# sap_flux-v21.net
KiCad netlist of a schematic drawn in EAGLE
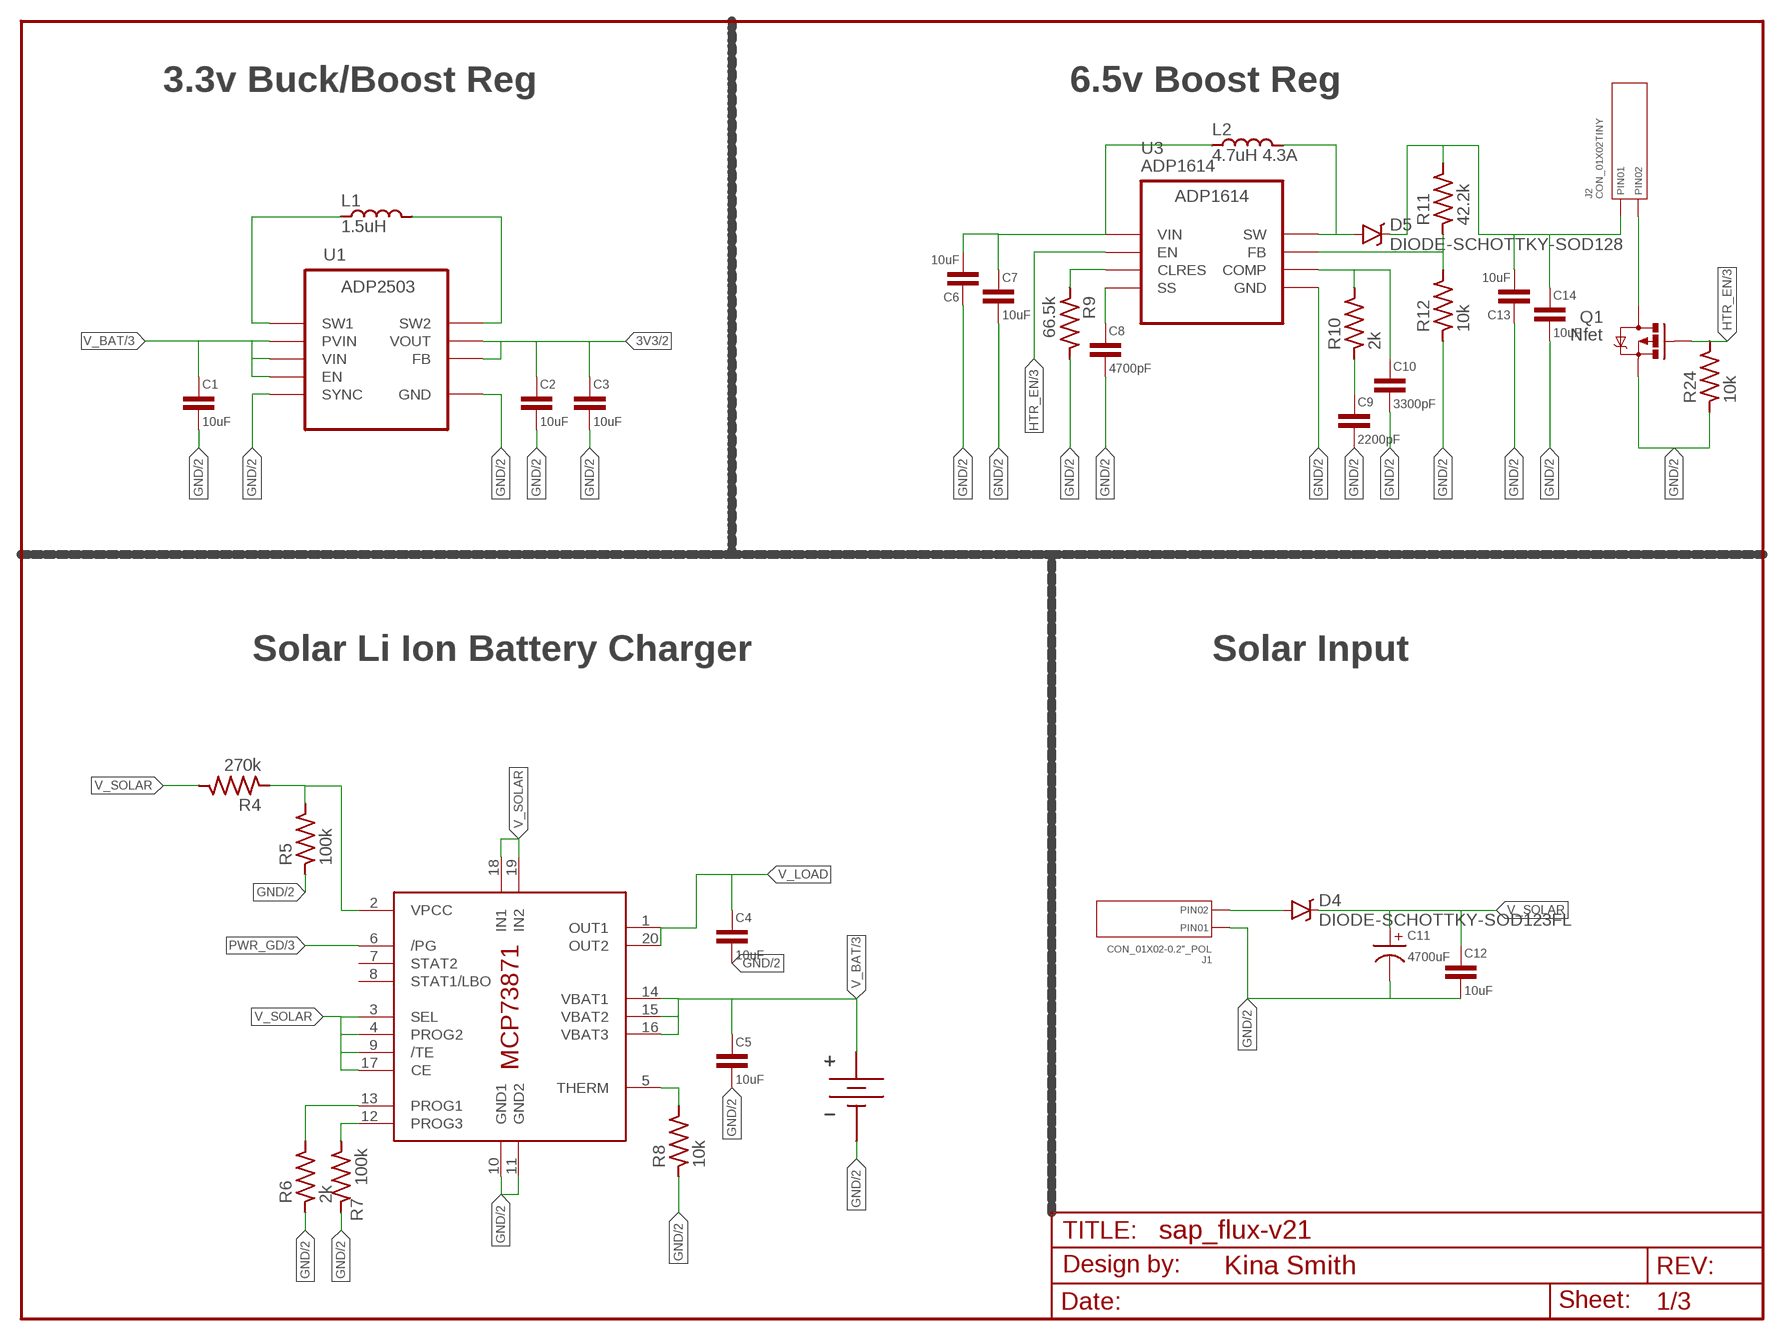
[diagram p0: schematic, sheet 1]
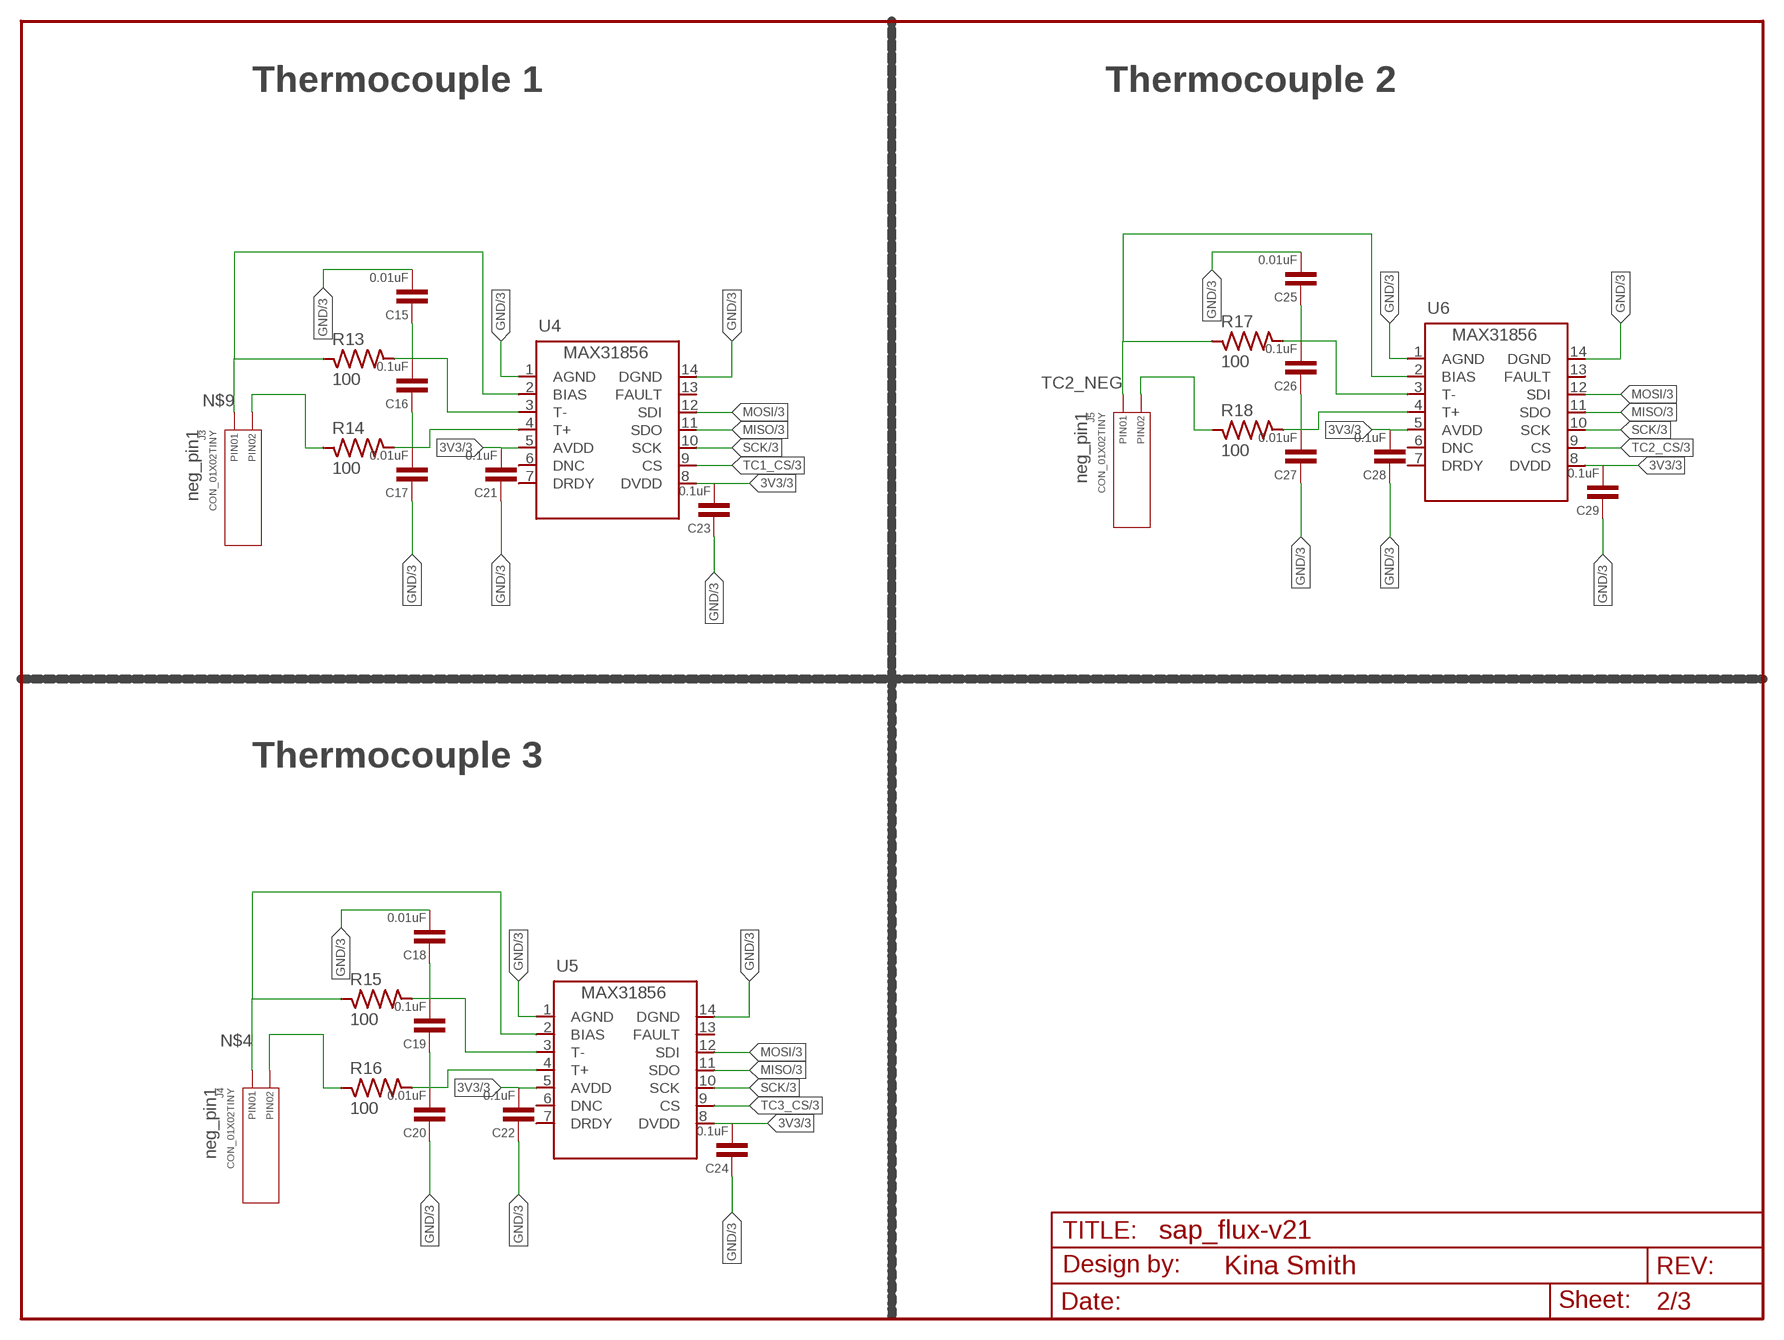
[diagram p1: schematic, sheet 2]
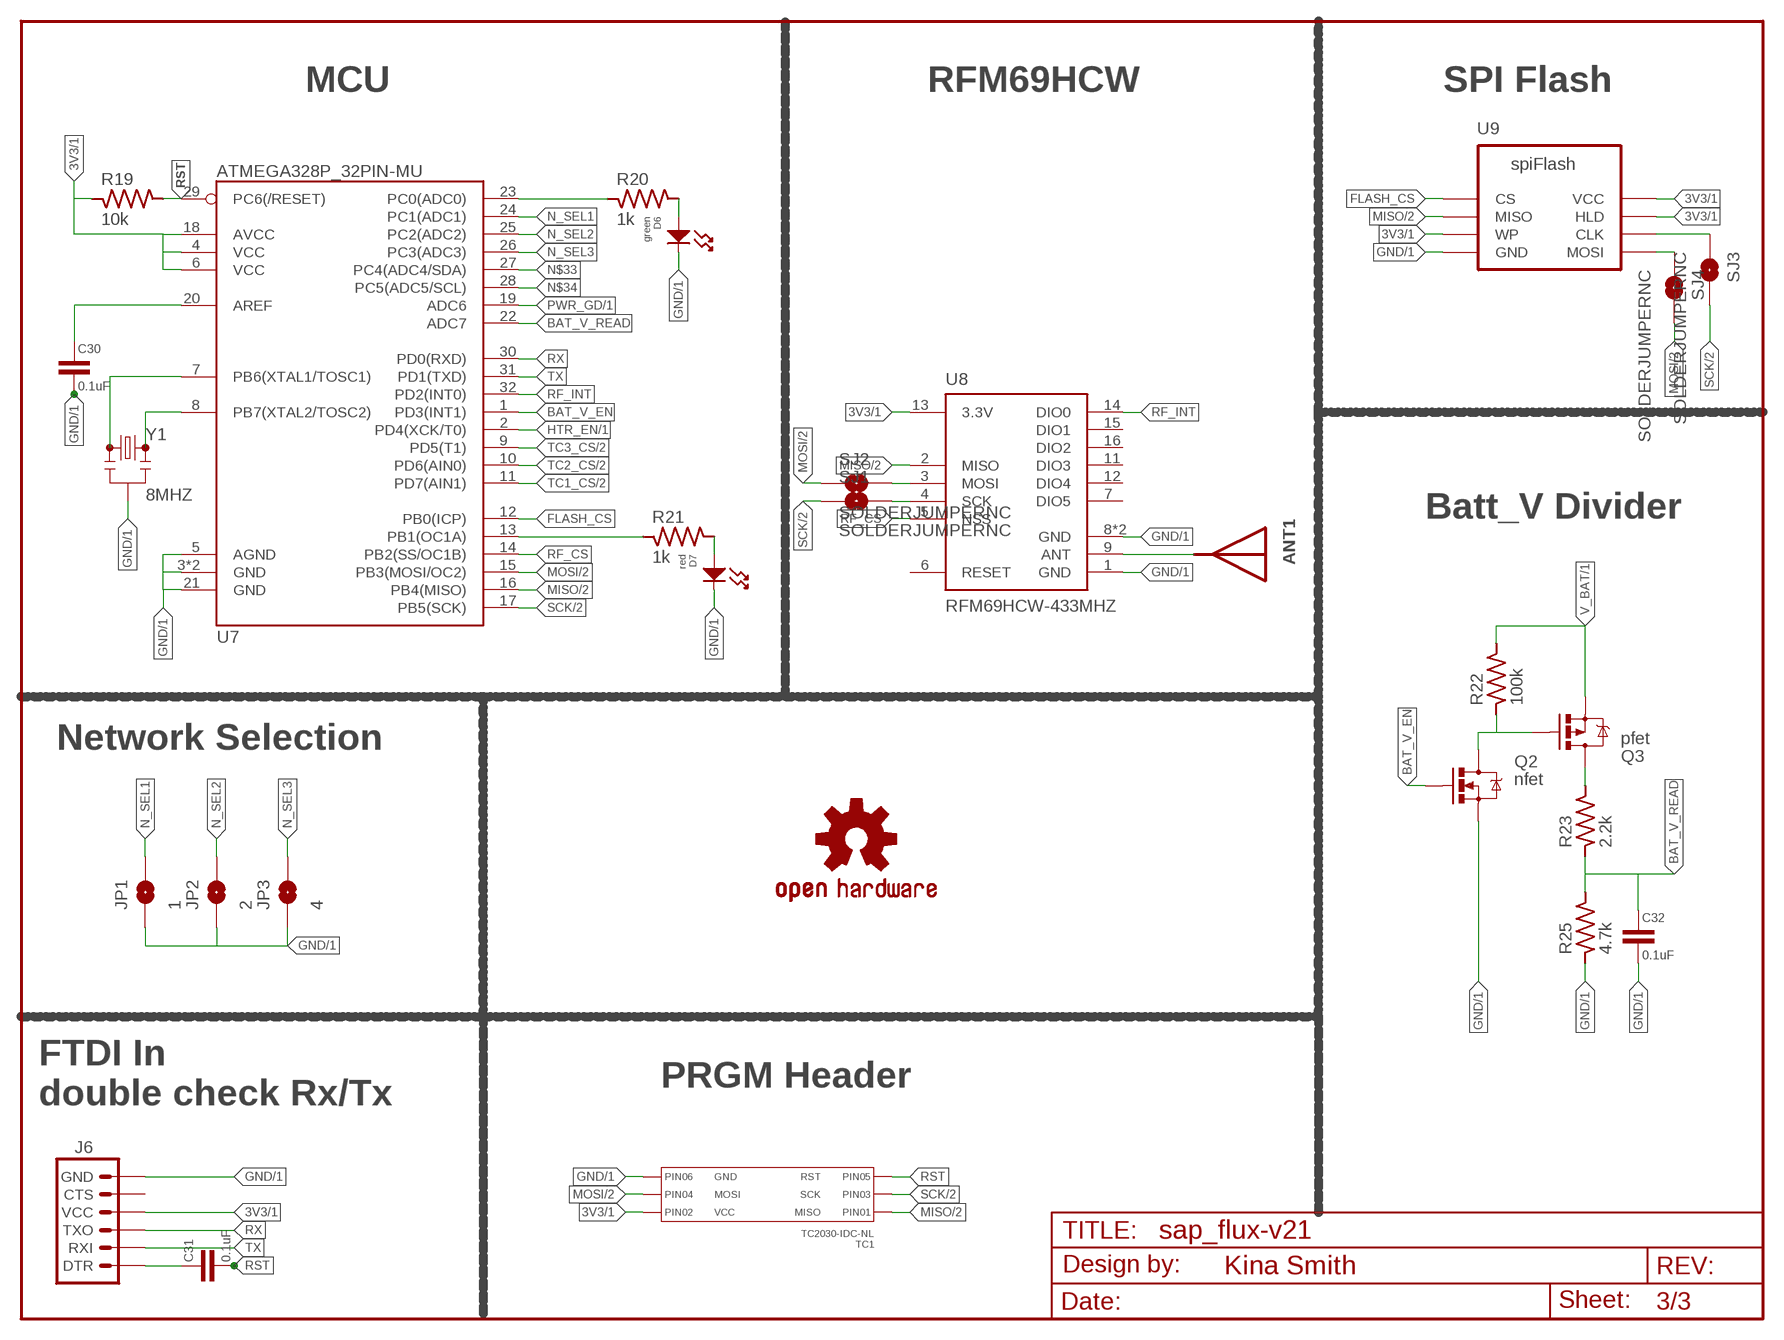
[diagram p2: schematic, sheet 3]

(export (version "E")
  (design (tool "Eeschema 10.0.6"))
  (components
    (comp (ref "BATT1")
      (value "BATTERY_HOLDER-18650_CLIP")
      (footprint "eagle-import:BAT_18650_CLIP")
      (fields (field (name "PARTNO") "54"))
      (libsource (lib "eagle-import") (part "BATTERY_HOLDER-18650_CLIP"))
    )
    (comp (ref "C1")
      (value "10uF")
      (footprint "eagle-import:C0805-N")
      (fields (field (name "PARTNO") "GRM21BR61C106KE15K"))
      (libsource (lib "eagle-import") (part "CAPACITOR_NP0805-N"))
    )
    (comp (ref "C2")
      (value "10uF")
      (footprint "eagle-import:C0805-N")
      (fields (field (name "PARTNO") "GRM21BR61C106KE15K"))
      (libsource (lib "eagle-import") (part "CAPACITOR_NP0805-N"))
    )
    (comp (ref "C3")
      (value "10uF")
      (footprint "eagle-import:C0805-N")
      (fields (field (name "PARTNO") "GRM21BR61C106KE15K"))
      (libsource (lib "eagle-import") (part "CAPACITOR_NP0805-N"))
    )
    (comp (ref "C4")
      (value "10uF")
      (footprint "eagle-import:C0805-N")
      (fields (field (name "PARTNO") "GRM21BR61C106KE15K"))
      (libsource (lib "eagle-import") (part "CAPACITOR_NP0805-N"))
    )
    (comp (ref "C5")
      (value "10uF")
      (footprint "eagle-import:C0805-N")
      (fields (field (name "PARTNO") "GRM21BR61C106KE15K"))
      (libsource (lib "eagle-import") (part "CAPACITOR_NP0805-N"))
    )
    (comp (ref "C6")
      (value "10uF")
      (footprint "eagle-import:C0805-N")
      (fields (field (name "PARTNO") "GRM21BR61C106KE15K"))
      (libsource (lib "eagle-import") (part "CAPACITOR_NP0805-N"))
    )
    (comp (ref "C7")
      (value "10uF")
      (footprint "eagle-import:C0805-N")
      (fields (field (name "PARTNO") "GRM21BR61C106KE15K"))
      (libsource (lib "eagle-import") (part "CAPACITOR_NP0805-N"))
    )
    (comp (ref "C8")
      (value "4700pF")
      (footprint "eagle-import:C0603-N")
      (fields (field (name "PARTNO") "GRM188R71C472KA01D"))
      (libsource (lib "eagle-import") (part "CAPACITOR_NP0603-N"))
    )
    (comp (ref "C9")
      (value "2200pF")
      (footprint "eagle-import:C0603-N")
      (fields (field (name "PARTNO") "GRM188R71C222KA01D"))
      (libsource (lib "eagle-import") (part "CAPACITOR_NP0603-N"))
    )
    (comp (ref "C10")
      (value "3300pF")
      (footprint "eagle-import:C0603-N")
      (fields (field (name "PARTNO") "C0603C332K4RACTU"))
      (libsource (lib "eagle-import") (part "CAPACITOR_NP0603-N"))
    )
    (comp (ref "C11")
      (value "4700uF")
      (footprint "eagle-import:CP_TH_5MM")
      (fields (field (name "PARTNO") "ECA-1AM472"))
      (libsource (lib "eagle-import") (part "CAPACITOR_P-TH_5MM"))
    )
    (comp (ref "C12")
      (value "10uF")
      (footprint "eagle-import:C0805-N")
      (fields (field (name "PARTNO") "GRM21BR61C106KE15K"))
      (libsource (lib "eagle-import") (part "CAPACITOR_NP0805-N"))
    )
    (comp (ref "C13")
      (value "10uF")
      (footprint "eagle-import:C0805-N")
      (fields (field (name "PARTNO") "GRM21BR61C106KE15K"))
      (libsource (lib "eagle-import") (part "CAPACITOR_NP0805-N"))
    )
    (comp (ref "C14")
      (value "10uF")
      (footprint "eagle-import:C0805-N")
      (fields (field (name "PARTNO") "GRM21BR61C106KE15K"))
      (libsource (lib "eagle-import") (part "CAPACITOR_NP0805-N"))
    )
    (comp (ref "D4")
      (value "DIODE-SCHOTTKY-SOD123FL")
      (footprint "eagle-import:SOD-123FL")
      (fields (field (name "PARTNO") "MBR120VLSFT1G"))
      (libsource (lib "eagle-import") (part "DIODE-SCHOTTKY-SOD123FL"))
    )
    (comp (ref "D5")
      (value "DIODE-SCHOTTKY-SOD128")
      (footprint "eagle-import:SOD128")
      (fields (field (name "PARTNO") "CMS05(TE12L,Q,M)"))
      (libsource (lib "eagle-import") (part "DIODE-SCHOTTKY-SOD128"))
    )
    (comp (ref "FRAME1")
      (value "FRAME-LETTER")
      (footprint "eagle-import:CREATIVE_COMMONS")
      (fields (field (name "PARTNO") "NA"))
      (libsource (lib "eagle-import") (part "FRAME-LETTER"))
    )
    (comp (ref "J1")
      (value "CON_01X02-0.2\"_POL")
      (footprint "eagle-import:1X02_SCREWTERM_0.2IN")
      (fields (field (name "PARTNO") "0398890042"))
      (libsource (lib "eagle-import") (part "CON_01X02-0.2{dblquote}_POL"))
    )
    (comp (ref "J2")
      (value "CON_01X02TINY")
      (footprint "eagle-import:1X02_TINY")
      (libsource (lib "eagle-import") (part "CON_01X02TINY"))
    )
    (comp (ref "L1")
      (value "1.5uH")
      (footprint "eagle-import:L3030")
      (fields (field (name "PARTNO") "NR3015T1R5N"))
      (libsource (lib "eagle-import") (part "INDUCTOR3030"))
    )
    (comp (ref "L2")
      (value "4.7uH 4.3A")
      (footprint "eagle-import:L8080")
      (fields (field (name "PARTNO") "NRS8040T100MJGJ"))
      (libsource (lib "eagle-import") (part "INDUCTOR8080"))
    )
    (comp (ref "Q1")
      (value "Nfet")
      (footprint "eagle-import:SOT23-3")
      (fields (field (name "PARTNO") "DMN2075U-7"))
      (libsource (lib "eagle-import") (part "MOSFET-PCHANNELSOT23-3"))
    )
    (comp (ref "R4")
      (value "270k")
      (footprint "eagle-import:R0603-N")
      (fields (field (name "PARTNO") "RC0603FR-07270KL"))
      (libsource (lib "eagle-import") (part "RESISTOR0603-N"))
    )
    (comp (ref "R5")
      (value "100k")
      (footprint "eagle-import:R0603-N")
      (fields (field (name "PARTNO") "RC0603FR-07100KL"))
      (libsource (lib "eagle-import") (part "RESISTOR0603-N"))
    )
    (comp (ref "R6")
      (value "2k")
      (footprint "eagle-import:R0603-N")
      (fields (field (name "PARTNO") "RC0603FR-072KL"))
      (libsource (lib "eagle-import") (part "RESISTOR0603-N"))
    )
    (comp (ref "R7")
      (value "100k")
      (footprint "eagle-import:R0603-N")
      (fields (field (name "PARTNO") "RC0603FR-07100KL"))
      (libsource (lib "eagle-import") (part "RESISTOR0603-N"))
    )
    (comp (ref "R8")
      (value "10k")
      (footprint "eagle-import:R0603-N")
      (fields (field (name "PARTNO") "RC0603FR-0710KL"))
      (libsource (lib "eagle-import") (part "RESISTOR0603-N"))
    )
    (comp (ref "R9")
      (value "66.5k")
      (footprint "eagle-import:R0603-N")
      (fields (field (name "PARTNO") "RC0603FR-0766K5L"))
      (libsource (lib "eagle-import") (part "RESISTOR0603-N"))
    )
    (comp (ref "R10")
      (value "2k")
      (footprint "eagle-import:R0603-N")
      (fields (field (name "PARTNO") "RC0603FR-072KL"))
      (libsource (lib "eagle-import") (part "RESISTOR0603-N"))
    )
    (comp (ref "R11")
      (value "42.2k")
      (footprint "eagle-import:R0603-N")
      (fields (field (name "PARTNO") "RC0603FR-0742K2L"))
      (libsource (lib "eagle-import") (part "RESISTOR0603-N"))
    )
    (comp (ref "R12")
      (value "10k")
      (footprint "eagle-import:R0603-N")
      (fields (field (name "PARTNO") "RC0603FR-0710KL"))
      (libsource (lib "eagle-import") (part "RESISTOR0603-N"))
    )
    (comp (ref "R24")
      (value "10k")
      (footprint "eagle-import:R0603-N")
      (fields (field (name "PARTNO") "RC0603FR-0710KL"))
      (libsource (lib "eagle-import") (part "RESISTOR0603-N"))
    )
    (comp (ref "U1")
      (value "ADP2503")
      (footprint "eagle-import:DFN300X300X80-11N")
      (fields (field (name "PARTNO") "ADP2503ACPZ-3.3-R7 ") (field (name "PARTNO_1") "ADP2503ACPZ-3.3-R7"))
      (libsource (lib "eagle-import") (part "ADP2503"))
    )
    (comp (ref "U2")
      (value "MCP73871")
      (footprint "eagle-import:QFN20")
      (fields (field (name "PARTNO") "MCP73871-2AAI/ML-ND"))
      (libsource (lib "eagle-import") (part "MCP73871"))
    )
    (comp (ref "U3")
      (value "ADP1614")
      (footprint "eagle-import:DFN300X300X80-11N")
      (fields (field (name "PARTNO") "ADP1614ACPZ-R7") (field (name "PARTNO_1") "ADP1614ACPZ-650-R7"))
      (libsource (lib "eagle-import") (part "ADP1614"))
    )
    (comp (ref "ANT1")
      (value "ANTENNA-433_CHIP")
      (footprint "eagle-import:ANT_433_CHIP")
      (fields (field (name "PARTNO") "0433AT62A0020E"))
      (libsource (lib "eagle-import") (part "ANTENNA-433_CHIP"))
    )
    (comp (ref "C30")
      (value "0.1uF")
      (footprint "eagle-import:C0603-N")
      (fields (field (name "PARTNO") "CC0603KRX7R7BB104"))
      (libsource (lib "eagle-import") (part "CAPACITOR_NP0603-N"))
    )
    (comp (ref "C31")
      (value "0.1uF")
      (footprint "eagle-import:C0603-N")
      (fields (field (name "PARTNO") "CC0603KRX7R7BB104"))
      (libsource (lib "eagle-import") (part "CAPACITOR_NP0603-N"))
    )
    (comp (ref "C32")
      (value "0.1uF")
      (footprint "eagle-import:C0603-N")
      (fields (field (name "PARTNO") "CC0603KRX7R7BB104"))
      (libsource (lib "eagle-import") (part "CAPACITOR_NP0603-N"))
    )
    (comp (ref "D6")
      (value "green")
      (footprint "eagle-import:LED0603")
      (fields (field (name "HOUSEPART") "NO") (field (name "PARTNO") "LTST-C191KGKT"))
      (libsource (lib "eagle-import") (part "LED_SINGLE-0603"))
    )
    (comp (ref "D7")
      (value "red")
      (footprint "eagle-import:LED0603")
      (fields (field (name "HOUSEPART") "NO") (field (name "PARTNO") "LTST-C191KRKT"))
      (libsource (lib "eagle-import") (part "LED_SINGLE-0603"))
    )
    (comp (ref "FRAME3")
      (value "FRAME-LETTERNO_PACKAGE")
      (footprint "eagle-import:DUMMY")
      (fields (field (name "PARTNO") "NA") (field (name "DESIGNER") "Nobody"))
      (libsource (lib "eagle-import") (part "FRAME-LETTERNO_PACKAGE"))
    )
    (comp (ref "J6")
      (value "ARDUINO_SERIAL_PROGRAMPTH")
      (footprint "eagle-import:1X06")
      (fields (field (name "PARTNO") "68001-106HLF"))
      (libsource (lib "eagle-import") (part "ARDUINO_SERIAL_PROGRAMPTH"))
    )
    (comp (ref "JP1")
      (value "1")
      (footprint "eagle-import:PAD-JUMPER-2-NO_YES_SILK")
      (fields (field (name "PARTNO") "NA"))
      (libsource (lib "eagle-import") (part "JUMPER-PAD-2-NOYES_SILK"))
    )
    (comp (ref "JP2")
      (value "2")
      (footprint "eagle-import:PAD-JUMPER-2-NO_YES_SILK")
      (fields (field (name "PARTNO") "NA"))
      (libsource (lib "eagle-import") (part "JUMPER-PAD-2-NOYES_SILK"))
    )
    (comp (ref "JP3")
      (value "4")
      (footprint "eagle-import:PAD-JUMPER-2-NO_YES_SILK")
      (fields (field (name "PARTNO") "NA"))
      (libsource (lib "eagle-import") (part "JUMPER-PAD-2-NOYES_SILK"))
    )
    (comp (ref "LOGO1")
      (value "OSHW-LOGOS-COPPER")
      (footprint "eagle-import:OSHW-LOGO-S_COPPER")
      (libsource (lib "eagle-import") (part "OSHW-LOGOS-COPPER"))
    )
    (comp (ref "Q2")
      (value "nfet")
      (footprint "eagle-import:SOT23-3")
      (fields (field (name "PARTNO") "BSS138"))
      (libsource (lib "eagle-import") (part "MOSFET-NCHANNELSOT23-3"))
    )
    (comp (ref "Q3")
      (value "pfet")
      (footprint "eagle-import:SOT23-3")
      (fields (field (name "PARTNO") "IRLML2244TRPBF"))
      (libsource (lib "eagle-import") (part "MOSFET-PCHANNELSOT23-3"))
    )
    (comp (ref "R19")
      (value "10k")
      (footprint "eagle-import:R0603-N")
      (fields (field (name "PARTNO") "RC0603FR-0710KL"))
      (libsource (lib "eagle-import") (part "RESISTOR0603-N"))
    )
    (comp (ref "R20")
      (value "1k")
      (footprint "eagle-import:R0603-N")
      (fields (field (name "PARTNO") "RC0603FR-071KL"))
      (libsource (lib "eagle-import") (part "RESISTOR0603-N"))
    )
    (comp (ref "R21")
      (value "1k")
      (footprint "eagle-import:R0603-N")
      (fields (field (name "PARTNO") "RC0603FR-071KL"))
      (libsource (lib "eagle-import") (part "RESISTOR0603-N"))
    )
    (comp (ref "R22")
      (value "100k")
      (footprint "eagle-import:R0603-N")
      (fields (field (name "PARTNO") "RC0603FR-07100KL"))
      (libsource (lib "eagle-import") (part "RESISTOR0603-N"))
    )
    (comp (ref "R23")
      (value "2.2k")
      (footprint "eagle-import:R0603-N")
      (fields (field (name "PARTNO") "RC0603FR-072K2L"))
      (libsource (lib "eagle-import") (part "RESISTOR0603-N"))
    )
    (comp (ref "R25")
      (value "4.7k")
      (footprint "eagle-import:R0603-N")
      (fields (field (name "PARTNO") "RC0603FR-074K7L"))
      (libsource (lib "eagle-import") (part "RESISTOR0603-N"))
    )
    (comp (ref "SJ1")
      (value "SOLDERJUMPERNC")
      (footprint "eagle-import:SJ_2S")
      (fields (field (name "PARTNO") "NA"))
      (libsource (lib "eagle-import") (part "SOLDERJUMPERNC"))
    )
    (comp (ref "SJ2")
      (value "SOLDERJUMPERNC")
      (footprint "eagle-import:SJ_2S")
      (fields (field (name "PARTNO") "NA"))
      (libsource (lib "eagle-import") (part "SOLDERJUMPERNC"))
    )
    (comp (ref "SJ3")
      (value "SOLDERJUMPERNC")
      (footprint "eagle-import:SJ_2S")
      (fields (field (name "PARTNO") "NA"))
      (libsource (lib "eagle-import") (part "SOLDERJUMPERNC"))
    )
    (comp (ref "SJ4")
      (value "SOLDERJUMPERNC")
      (footprint "eagle-import:SJ_2S")
      (fields (field (name "PARTNO") "NA"))
      (libsource (lib "eagle-import") (part "SOLDERJUMPERNC"))
    )
    (comp (ref "TC1")
      (value "TC2030-IDC-NL")
      (footprint "eagle-import:TC2030-IDC-NL")
      (fields (field (name "HOUSEPART") "NO") (field (name "PARTNO") "NA"))
      (libsource (lib "eagle-import") (part "CON_02X03_TC2030-IDC-NL_AVRISP"))
    )
    (comp (ref "U7")
      (value "ATMEGA328P_32PIN-MU")
      (footprint "eagle-import:MLF32_RECTPADS")
      (fields (field (name "PARTNO") "ATMEGA328P-MU"))
      (libsource (lib "eagle-import") (part "ATMEGA328P_32PIN-MU"))
    )
    (comp (ref "U8")
      (value "RFM69HCW-433MHZ")
      (footprint "eagle-import:RFM69HCW-XXXS2")
      (fields (field (name "PARTNO") "COM-13910"))
      (libsource (lib "eagle-import") (part "RFM69HCW-433MHZ"))
    )
    (comp (ref "U9")
      (value "WINBOND_FLASH_4MBIT-SOIC")
      (footprint "eagle-import:SOIC8")
      (fields (field (name "PARTNO") "W25X40CLSNIG"))
      (libsource (lib "eagle-import") (part "WINBOND_FLASH_4MBIT-SOIC"))
    )
    (comp (ref "Y1")
      (value "8MHZ")
      (footprint "eagle-import:RESONATOR-SMD")
      (fields (field (name "PARTNO") "CSTCE8M00G55-R0"))
      (libsource (lib "eagle-import") (part "RESONATOR8MHZ"))
    )
    (comp (ref "C15")
      (value "0.01uF")
      (footprint "eagle-import:C0603-N")
      (fields (field (name "PARTNO") "GRM188R71C103KA01D"))
      (libsource (lib "eagle-import") (part "CAPACITOR_NP0603-N"))
    )
    (comp (ref "C16")
      (value "0.1uF")
      (footprint "eagle-import:C0603-N")
      (fields (field (name "PARTNO") "CC0603KRX7R7BB104"))
      (libsource (lib "eagle-import") (part "CAPACITOR_NP0603-N"))
    )
    (comp (ref "C17")
      (value "0.01uF")
      (footprint "eagle-import:C0603-N")
      (fields (field (name "PARTNO") "GRM188R71C103KA01D"))
      (libsource (lib "eagle-import") (part "CAPACITOR_NP0603-N"))
    )
    (comp (ref "C18")
      (value "0.01uF")
      (footprint "eagle-import:C0603-N")
      (fields (field (name "PARTNO") "GRM188R71C103KA01D"))
      (libsource (lib "eagle-import") (part "CAPACITOR_NP0603-N"))
    )
    (comp (ref "C19")
      (value "0.1uF")
      (footprint "eagle-import:C0603-N")
      (fields (field (name "PARTNO") "CC0603KRX7R7BB104"))
      (libsource (lib "eagle-import") (part "CAPACITOR_NP0603-N"))
    )
    (comp (ref "C20")
      (value "0.01uF")
      (footprint "eagle-import:C0603-N")
      (fields (field (name "PARTNO") "GRM188R71C103KA01D"))
      (libsource (lib "eagle-import") (part "CAPACITOR_NP0603-N"))
    )
    (comp (ref "C21")
      (value "0.1uF")
      (footprint "eagle-import:C0603-N")
      (fields (field (name "PARTNO") "CC0603KRX7R7BB104"))
      (libsource (lib "eagle-import") (part "CAPACITOR_NP0603-N"))
    )
    (comp (ref "C22")
      (value "0.1uF")
      (footprint "eagle-import:C0603-N")
      (fields (field (name "PARTNO") "CC0603KRX7R7BB104"))
      (libsource (lib "eagle-import") (part "CAPACITOR_NP0603-N"))
    )
    (comp (ref "C23")
      (value "0.1uF")
      (footprint "eagle-import:C0603-N")
      (fields (field (name "PARTNO") "CC0603KRX7R7BB104"))
      (libsource (lib "eagle-import") (part "CAPACITOR_NP0603-N"))
    )
    (comp (ref "C24")
      (value "0.1uF")
      (footprint "eagle-import:C0603-N")
      (fields (field (name "PARTNO") "CC0603KRX7R7BB104"))
      (libsource (lib "eagle-import") (part "CAPACITOR_NP0603-N"))
    )
    (comp (ref "C25")
      (value "0.01uF")
      (footprint "eagle-import:C0603-N")
      (fields (field (name "PARTNO") "GRM188R71C103KA01D"))
      (libsource (lib "eagle-import") (part "CAPACITOR_NP0603-N"))
    )
    (comp (ref "C26")
      (value "0.1uF")
      (footprint "eagle-import:C0603-N")
      (fields (field (name "PARTNO") "CC0603KRX7R7BB104"))
      (libsource (lib "eagle-import") (part "CAPACITOR_NP0603-N"))
    )
    (comp (ref "C27")
      (value "0.01uF")
      (footprint "eagle-import:C0603-N")
      (fields (field (name "PARTNO") "GRM188R71C103KA01D"))
      (libsource (lib "eagle-import") (part "CAPACITOR_NP0603-N"))
    )
    (comp (ref "C28")
      (value "0.1uF")
      (footprint "eagle-import:C0603-N")
      (fields (field (name "PARTNO") "CC0603KRX7R7BB104"))
      (libsource (lib "eagle-import") (part "CAPACITOR_NP0603-N"))
    )
    (comp (ref "C29")
      (value "0.1uF")
      (footprint "eagle-import:C0603-N")
      (fields (field (name "PARTNO") "CC0603KRX7R7BB104"))
      (libsource (lib "eagle-import") (part "CAPACITOR_NP0603-N"))
    )
    (comp (ref "FRAME2")
      (value "FRAME-LETTERNO_PACKAGE")
      (footprint "eagle-import:DUMMY")
      (fields (field (name "PARTNO") "NA") (field (name "DESIGNER") "Nobody"))
      (libsource (lib "eagle-import") (part "FRAME-LETTERNO_PACKAGE"))
    )
    (comp (ref "J3")
      (value "CON_01X02TINY")
      (footprint "eagle-import:1X02_TINY")
      (fields (field (name "NOTE") "neg_pin1"))
      (libsource (lib "eagle-import") (part "CON_01X02TINY"))
    )
    (comp (ref "J4")
      (value "CON_01X02TINY")
      (footprint "eagle-import:1X02_TINY")
      (fields (field (name "NOTE") "neg_pin1"))
      (libsource (lib "eagle-import") (part "CON_01X02TINY"))
    )
    (comp (ref "J5")
      (value "CON_01X02TINY")
      (footprint "eagle-import:1X02_TINY")
      (fields (field (name "NOTE") "neg_pin1"))
      (libsource (lib "eagle-import") (part "CON_01X02TINY"))
    )
    (comp (ref "R13")
      (value "100")
      (footprint "eagle-import:R0603-N")
      (fields (field (name "PARTNO") "RC0603FR-07100RL"))
      (libsource (lib "eagle-import") (part "RESISTOR0603-N"))
    )
    (comp (ref "R14")
      (value "100")
      (footprint "eagle-import:R0603-N")
      (fields (field (name "PARTNO") "RC0603FR-07100RL"))
      (libsource (lib "eagle-import") (part "RESISTOR0603-N"))
    )
    (comp (ref "R15")
      (value "100")
      (footprint "eagle-import:R0603-N")
      (fields (field (name "PARTNO") "RC0603FR-07100RL"))
      (libsource (lib "eagle-import") (part "RESISTOR0603-N"))
    )
    (comp (ref "R16")
      (value "100")
      (footprint "eagle-import:R0603-N")
      (fields (field (name "PARTNO") "RC0603FR-07100RL"))
      (libsource (lib "eagle-import") (part "RESISTOR0603-N"))
    )
    (comp (ref "R17")
      (value "100")
      (footprint "eagle-import:R0603-N")
      (fields (field (name "PARTNO") "RC0603FR-07100RL"))
      (libsource (lib "eagle-import") (part "RESISTOR0603-N"))
    )
    (comp (ref "R18")
      (value "100")
      (footprint "eagle-import:R0603-N")
      (fields (field (name "PARTNO") "RC0603FR-07100RL"))
      (libsource (lib "eagle-import") (part "RESISTOR0603-N"))
    )
    (comp (ref "U4")
      (value "MAX31856MUD+")
      (footprint "eagle-import:TSSOP14")
      (libsource (lib "eagle-import") (part "MAX31856MUD+"))
    )
    (comp (ref "U5")
      (value "MAX31856MUD+")
      (footprint "eagle-import:TSSOP14")
      (libsource (lib "eagle-import") (part "MAX31856MUD+"))
    )
    (comp (ref "U6")
      (value "MAX31856MUD+")
      (footprint "eagle-import:TSSOP14")
      (libsource (lib "eagle-import") (part "MAX31856MUD+"))
    )
  )
  (nets
    (net (code "1") (name "3V3") (class "Default")
      (node (ref "C2") (pin "1") (pinfunction "1_1") (pintype "passive"))
      (node (ref "C21") (pin "2") (pinfunction "2_2") (pintype "passive"))
      (node (ref "C22") (pin "2") (pinfunction "2_2") (pintype "passive"))
      (node (ref "C23") (pin "2") (pinfunction "2_2") (pintype "passive"))
      (node (ref "C24") (pin "2") (pinfunction "2_2") (pintype "passive"))
      (node (ref "C28") (pin "2") (pinfunction "2_2") (pintype "passive"))
      (node (ref "C29") (pin "2") (pinfunction "2_2") (pintype "passive"))
      (node (ref "C3") (pin "1") (pinfunction "1_1") (pintype "passive"))
      (node (ref "J6") (pin "4") (pinfunction "VCC_4") (pintype "passive"))
      (node (ref "R19") (pin "1") (pinfunction "P$1_1") (pintype "passive"))
      (node (ref "TC1") (pin "P$2") (pinfunction "PIN2_P$2") (pintype "bidirectional"))
      (node (ref "U1") (pin "1") (pinfunction "VOUT_1") (pintype "bidirectional"))
      (node (ref "U1") (pin "10") (pinfunction "FB_10") (pintype "bidirectional"))
      (node (ref "U4") (pin "5") (pinfunction "AVDD_5") (pintype "bidirectional"))
      (node (ref "U4") (pin "8") (pinfunction "DVDD_8") (pintype "bidirectional"))
      (node (ref "U5") (pin "5") (pinfunction "AVDD_5") (pintype "bidirectional"))
      (node (ref "U5") (pin "8") (pinfunction "DVDD_8") (pintype "bidirectional"))
      (node (ref "U6") (pin "5") (pinfunction "AVDD_5") (pintype "bidirectional"))
      (node (ref "U6") (pin "8") (pinfunction "DVDD_8") (pintype "bidirectional"))
      (node (ref "U7") (pin "18") (pinfunction "AVCC_18") (pintype "bidirectional"))
      (node (ref "U7") (pin "4") (pinfunction "VCC_4") (pintype "bidirectional"))
      (node (ref "U7") (pin "6") (pinfunction "VCC_6") (pintype "bidirectional"))
      (node (ref "U8") (pin "13") (pinfunction "3.3V_13") (pintype "power_in"))
      (node (ref "U9") (pin "3") (pinfunction "WP_3") (pintype "bidirectional"))
      (node (ref "U9") (pin "7") (pinfunction "HLD_7") (pintype "bidirectional"))
      (node (ref "U9") (pin "8") (pinfunction "VCC_8") (pintype "bidirectional"))
    )
    (net (code "2") (name "BAT_V_EN") (class "Default")
      (node (ref "Q2") (pin "1") (pinfunction "G_1") (pintype "passive"))
      (node (ref "U7") (pin "1") (pinfunction "PD3(INT1)_1") (pintype "bidirectional"))
    )
    (net (code "3") (name "BAT_V_READ") (class "Default")
      (node (ref "C32") (pin "1") (pinfunction "1_1") (pintype "passive"))
      (node (ref "R23") (pin "1") (pinfunction "P$1_1") (pintype "passive"))
      (node (ref "R25") (pin "2") (pinfunction "P$2_2") (pintype "passive"))
      (node (ref "U7") (pin "22") (pinfunction "ADC7_22") (pintype "bidirectional"))
    )
    (net (code "4") (name "FLASH_CS") (class "Default")
      (node (ref "U7") (pin "12") (pinfunction "PB0(ICP)_12") (pintype "bidirectional"))
      (node (ref "U9") (pin "1") (pinfunction "CS_1") (pintype "bidirectional"))
    )
    (net (code "5") (name "GND") (class "Default")
      (node (ref "BATT1") (pin "NEG_1") (pinfunction "GND_NEG_1") (pintype "bidirectional"))
      (node (ref "BATT1") (pin "NEG_2") (pinfunction "GND_NEG_2") (pintype "bidirectional"))
      (node (ref "BATT1") (pin "NEG_3") (pinfunction "GND_NEG_3") (pintype "bidirectional"))
      (node (ref "C1") (pin "2") (pinfunction "2_2") (pintype "passive"))
      (node (ref "C10") (pin "2") (pinfunction "2_2") (pintype "passive"))
      (node (ref "C11") (pin "NEG") (pinfunction "NEG_NEG") (pintype "passive"))
      (node (ref "C12") (pin "2") (pinfunction "2_2") (pintype "passive"))
      (node (ref "C13") (pin "1") (pinfunction "1_1") (pintype "passive"))
      (node (ref "C14") (pin "2") (pinfunction "2_2") (pintype "passive"))
      (node (ref "C15") (pin "2") (pinfunction "2_2") (pintype "passive"))
      (node (ref "C17") (pin "1") (pinfunction "1_1") (pintype "passive"))
      (node (ref "C18") (pin "2") (pinfunction "2_2") (pintype "passive"))
      (node (ref "C2") (pin "2") (pinfunction "2_2") (pintype "passive"))
      (node (ref "C20") (pin "1") (pinfunction "1_1") (pintype "passive"))
      (node (ref "C21") (pin "1") (pinfunction "1_1") (pintype "passive"))
      (node (ref "C22") (pin "1") (pinfunction "1_1") (pintype "passive"))
      (node (ref "C23") (pin "1") (pinfunction "1_1") (pintype "passive"))
      (node (ref "C24") (pin "1") (pinfunction "1_1") (pintype "passive"))
      (node (ref "C25") (pin "2") (pinfunction "2_2") (pintype "passive"))
      (node (ref "C27") (pin "1") (pinfunction "1_1") (pintype "passive"))
      (node (ref "C28") (pin "1") (pinfunction "1_1") (pintype "passive"))
      (node (ref "C29") (pin "1") (pinfunction "1_1") (pintype "passive"))
      (node (ref "C3") (pin "2") (pinfunction "2_2") (pintype "passive"))
      (node (ref "C30") (pin "2") (pinfunction "2_2") (pintype "passive"))
      (node (ref "C32") (pin "2") (pinfunction "2_2") (pintype "passive"))
      (node (ref "C4") (pin "2") (pinfunction "2_2") (pintype "passive"))
      (node (ref "C5") (pin "2") (pinfunction "2_2") (pintype "passive"))
      (node (ref "C6") (pin "1") (pinfunction "1_1") (pintype "passive"))
      (node (ref "C7") (pin "2") (pinfunction "2_2") (pintype "passive"))
      (node (ref "C8") (pin "2") (pinfunction "2_2") (pintype "passive"))
      (node (ref "C9") (pin "2") (pinfunction "2_2") (pintype "passive"))
      (node (ref "D6") (pin "CATHODE") (pinfunction "CATHODE_CATHODE") (pintype "power_in"))
      (node (ref "D7") (pin "CATHODE") (pinfunction "CATHODE_CATHODE") (pintype "power_in"))
      (node (ref "J1") (pin "NEG") (pinfunction "PIN1_NEG") (pintype "bidirectional"))
      (node (ref "J6") (pin "6") (pinfunction "GND_6") (pintype "passive"))
      (node (ref "JP1") (pin "1") (pinfunction "1_1") (pintype "passive"))
      (node (ref "JP2") (pin "1") (pinfunction "1_1") (pintype "passive"))
      (node (ref "JP3") (pin "1") (pinfunction "1_1") (pintype "passive"))
      (node (ref "Q1") (pin "2") (pinfunction "S_2") (pintype "passive"))
      (node (ref "Q2") (pin "2") (pinfunction "S_2") (pintype "passive"))
      (node (ref "R12") (pin "1") (pinfunction "P$1_1") (pintype "passive"))
      (node (ref "R24") (pin "1") (pinfunction "P$1_1") (pintype "passive"))
      (node (ref "R25") (pin "1") (pinfunction "P$1_1") (pintype "passive"))
      (node (ref "R5") (pin "1") (pinfunction "P$1_1") (pintype "passive"))
      (node (ref "R6") (pin "1") (pinfunction "P$1_1") (pintype "passive"))
      (node (ref "R7") (pin "1") (pinfunction "P$1_1") (pintype "passive"))
      (node (ref "R8") (pin "1") (pinfunction "P$1_1") (pintype "passive"))
      (node (ref "R9") (pin "2") (pinfunction "P$2_2") (pintype "passive"))
      (node (ref "TC1") (pin "P$6") (pinfunction "PIN6_P$6") (pintype "bidirectional"))
      (node (ref "U1") (pin "11") (pinfunction "GND_11") (pintype "bidirectional"))
      (node (ref "U1") (pin "3") (pinfunction "GND_3") (pintype "bidirectional"))
      (node (ref "U1") (pin "7") (pinfunction "SYNC_7") (pintype "bidirectional"))
      (node (ref "U1") (pin "9") (pinfunction "GND_9") (pintype "bidirectional"))
      (node (ref "U2") (pin "10") (pinfunction "GND1_10") (pintype "power_in"))
      (node (ref "U2") (pin "11") (pinfunction "GND2_11") (pintype "power_in"))
      (node (ref "U3") (pin "11") (pinfunction "GND_11") (pintype "bidirectional"))
      (node (ref "U3") (pin "4") (pinfunction "GND_4") (pintype "bidirectional"))
      (node (ref "U3") (pin "5") (pinfunction "GND_5") (pintype "bidirectional"))
      (node (ref "U4") (pin "1") (pinfunction "AGND_1") (pintype "bidirectional"))
      (node (ref "U4") (pin "14") (pinfunction "DGND_14") (pintype "bidirectional"))
      (node (ref "U5") (pin "1") (pinfunction "AGND_1") (pintype "bidirectional"))
      (node (ref "U5") (pin "14") (pinfunction "DGND_14") (pintype "bidirectional"))
      (node (ref "U6") (pin "1") (pinfunction "AGND_1") (pintype "bidirectional"))
      (node (ref "U6") (pin "14") (pinfunction "DGND_14") (pintype "bidirectional"))
      (node (ref "U7") (pin "21") (pinfunction "GND_21") (pintype "bidirectional"))
      (node (ref "U7") (pin "3") (pinfunction "GND_3") (pintype "bidirectional"))
      (node (ref "U7") (pin "5") (pinfunction "AGND_5") (pintype "bidirectional"))
      (node (ref "U7") (pin "PAD") (pinfunction "GND_PAD") (pintype "bidirectional"))
      (node (ref "U8") (pin "1") (pinfunction "GND_1") (pintype "power_in"))
      (node (ref "U8") (pin "10") (pinfunction "GND_10") (pintype "power_in"))
      (node (ref "U8") (pin "8") (pinfunction "GND_8") (pintype "power_in"))
      (node (ref "U9") (pin "4") (pinfunction "GND_4") (pintype "bidirectional"))
      (node (ref "Y1") (pin "2") (pinfunction "2_2") (pintype "passive"))
    )
    (net (code "6") (name "HTR_EN") (class "Default")
      (node (ref "Q1") (pin "1") (pinfunction "G_1") (pintype "passive"))
      (node (ref "R24") (pin "2") (pinfunction "P$2_2") (pintype "passive"))
      (node (ref "U3") (pin "3") (pinfunction "EN_3") (pintype "bidirectional"))
      (node (ref "U7") (pin "2") (pinfunction "PD4(XCK/T0)_2") (pintype "bidirectional"))
    )
    (net (code "7") (name "MISO") (class "Default")
      (node (ref "TC1") (pin "P$1") (pinfunction "PIN1_P$1") (pintype "bidirectional"))
      (node (ref "U4") (pin "11") (pinfunction "SDO_11") (pintype "bidirectional"))
      (node (ref "U5") (pin "11") (pinfunction "SDO_11") (pintype "bidirectional"))
      (node (ref "U6") (pin "11") (pinfunction "SDO_11") (pintype "bidirectional"))
      (node (ref "U7") (pin "16") (pinfunction "PB4(MISO)_16") (pintype "bidirectional"))
      (node (ref "U8") (pin "2") (pinfunction "MISO_2") (pintype "bidirectional"))
      (node (ref "U9") (pin "2") (pinfunction "MISO_2") (pintype "bidirectional"))
    )
    (net (code "8") (name "MOSI") (class "Default")
      (node (ref "SJ2") (pin "1") (pinfunction "1_1") (pintype "passive"))
      (node (ref "SJ4") (pin "2") (pinfunction "2_2") (pintype "passive"))
      (node (ref "TC1") (pin "P$4") (pinfunction "PIN4_P$4") (pintype "bidirectional"))
      (node (ref "U4") (pin "12") (pinfunction "SDI_12") (pintype "bidirectional"))
      (node (ref "U5") (pin "12") (pinfunction "SDI_12") (pintype "bidirectional"))
      (node (ref "U6") (pin "12") (pinfunction "SDI_12") (pintype "bidirectional"))
      (node (ref "U7") (pin "15") (pinfunction "PB3(MOSI/OC2)_15") (pintype "bidirectional"))
    )
    (net (code "9") (name "N$4") (class "Default")
      (node (ref "J4") (pin "NEG") (pinfunction "PIN1_NEG") (pintype "bidirectional"))
      (node (ref "R15") (pin "1") (pinfunction "P$1_1") (pintype "passive"))
      (node (ref "U5") (pin "2") (pinfunction "BIAS_2") (pintype "bidirectional"))
    )
    (net (code "10") (name "N$9") (class "Default")
      (node (ref "J3") (pin "NEG") (pinfunction "PIN1_NEG") (pintype "bidirectional"))
      (node (ref "R13") (pin "1") (pinfunction "P$1_1") (pintype "passive"))
      (node (ref "U4") (pin "2") (pinfunction "BIAS_2") (pintype "bidirectional"))
    )
    (net (code "11") (name "N$33") (class "Default")
      (node (ref "U7") (pin "27") (pinfunction "PC4(ADC4/SDA)_27") (pintype "bidirectional"))
    )
    (net (code "12") (name "N$34") (class "Default")
      (node (ref "U7") (pin "28") (pinfunction "PC5(ADC5/SCL)_28") (pintype "bidirectional"))
    )
    (net (code "13") (name "N_SEL1") (class "Default")
      (node (ref "JP1") (pin "2") (pinfunction "2_2") (pintype "passive"))
      (node (ref "U7") (pin "24") (pinfunction "PC1(ADC1)_24") (pintype "bidirectional"))
    )
    (net (code "14") (name "N_SEL2") (class "Default")
      (node (ref "JP2") (pin "2") (pinfunction "2_2") (pintype "passive"))
      (node (ref "U7") (pin "25") (pinfunction "PC2(ADC2)_25") (pintype "bidirectional"))
    )
    (net (code "15") (name "N_SEL3") (class "Default")
      (node (ref "JP3") (pin "2") (pinfunction "2_2") (pintype "passive"))
      (node (ref "U7") (pin "26") (pinfunction "PC3(ADC3)_26") (pintype "bidirectional"))
    )
    (net (code "16") (name "Net-(D5-A)") (class "Default")
      (node (ref "D5") (pin "A-2") (pinfunction "A_A-2") (pintype "passive"))
      (node (ref "L2") (pin "2") (pinfunction "P$2_2") (pintype "passive"))
      (node (ref "U3") (pin "6") (pinfunction "SW_6") (pintype "bidirectional"))
      (node (ref "U3") (pin "7") (pinfunction "SW_7") (pintype "bidirectional"))
    )
    (net (code "17") (name "Net-(D5-C)") (class "Default")
      (node (ref "C13") (pin "2") (pinfunction "2_2") (pintype "passive"))
      (node (ref "C14") (pin "1") (pinfunction "1_1") (pintype "passive"))
      (node (ref "D5") (pin "C-1") (pinfunction "C_C-1") (pintype "passive"))
      (node (ref "J2") (pin "NEG") (pinfunction "PIN1_NEG") (pintype "bidirectional"))
      (node (ref "R11") (pin "2") (pinfunction "P$2_2") (pintype "passive"))
    )
    (net (code "18") (name "Net-(J1-PIN2)") (class "Default")
      (node (ref "D4") (pin "A") (pinfunction "A_A") (pintype "passive"))
      (node (ref "J1") (pin "POS") (pinfunction "PIN2_POS") (pintype "bidirectional"))
    )
    (net (code "19") (name "Net-(J2-PIN2)") (class "Default")
      (node (ref "J2") (pin "POS") (pinfunction "PIN2_POS") (pintype "bidirectional"))
      (node (ref "Q1") (pin "3") (pinfunction "D_3") (pintype "passive"))
    )
    (net (code "20") (name "Net-(J3-PIN2)") (class "Default")
      (node (ref "J3") (pin "POS") (pinfunction "PIN2_POS") (pintype "bidirectional"))
      (node (ref "R14") (pin "1") (pinfunction "P$1_1") (pintype "passive"))
    )
    (net (code "21") (name "Net-(J4-PIN2)") (class "Default")
      (node (ref "J4") (pin "POS") (pinfunction "PIN2_POS") (pintype "bidirectional"))
      (node (ref "R16") (pin "1") (pinfunction "P$1_1") (pintype "passive"))
    )
    (net (code "22") (name "Net-(J5-PIN2)") (class "Default")
      (node (ref "J5") (pin "POS") (pinfunction "PIN2_POS") (pintype "bidirectional"))
      (node (ref "R18") (pin "1") (pinfunction "P$1_1") (pintype "passive"))
    )
    (net (code "23") (name "Net-(J6-DTR)") (class "Default")
      (node (ref "C31") (pin "1") (pinfunction "1_1") (pintype "passive"))
      (node (ref "J6") (pin "1") (pinfunction "DTR_1") (pintype "passive"))
    )
    (net (code "24") (name "Net-(Q2-D)") (class "Default")
      (node (ref "Q2") (pin "3") (pinfunction "D_3") (pintype "passive"))
      (node (ref "Q3") (pin "1") (pinfunction "G_1") (pintype "passive"))
      (node (ref "R22") (pin "1") (pinfunction "P$1_1") (pintype "passive"))
    )
    (net (code "25") (name "Net-(Q3-D)") (class "Default")
      (node (ref "Q3") (pin "3") (pinfunction "D_3") (pintype "passive"))
      (node (ref "R23") (pin "2") (pinfunction "P$2_2") (pintype "passive"))
    )
    (net (code "26") (name "Net-(R4-P$1)") (class "Default")
      (node (ref "R4") (pin "1") (pinfunction "P$1_1") (pintype "passive"))
      (node (ref "R5") (pin "2") (pinfunction "P$2_2") (pintype "passive"))
      (node (ref "U2") (pin "2") (pinfunction "VPCC_2") (pintype "input"))
    )
    (net (code "27") (name "Net-(R6-P$2)") (class "Default")
      (node (ref "R6") (pin "2") (pinfunction "P$2_2") (pintype "passive"))
      (node (ref "U2") (pin "13") (pinfunction "PROG1_13") (pintype "input"))
    )
    (net (code "28") (name "Net-(R7-P$2)") (class "Default")
      (node (ref "R7") (pin "2") (pinfunction "P$2_2") (pintype "passive"))
      (node (ref "U2") (pin "12") (pinfunction "PROG3_12") (pintype "input"))
    )
    (net (code "29") (name "Net-(R8-P$2)") (class "Default")
      (node (ref "R8") (pin "2") (pinfunction "P$2_2") (pintype "passive"))
      (node (ref "U2") (pin "5") (pinfunction "THERM_5") (pintype "input"))
    )
    (net (code "30") (name "Net-(R9-P$1)") (class "Default")
      (node (ref "R9") (pin "1") (pinfunction "P$1_1") (pintype "passive"))
      (node (ref "U3") (pin "9") (pinfunction "CLRES_9") (pintype "bidirectional"))
    )
    (net (code "31") (name "Net-(R10-P$1)") (class "Default")
      (node (ref "C9") (pin "1") (pinfunction "1_1") (pintype "passive"))
      (node (ref "R10") (pin "1") (pinfunction "P$1_1") (pintype "passive"))
    )
    (net (code "32") (name "Net-(R10-P$2)") (class "Default")
      (node (ref "C10") (pin "1") (pinfunction "1_1") (pintype "passive"))
      (node (ref "R10") (pin "2") (pinfunction "P$2_2") (pintype "passive"))
      (node (ref "U3") (pin "1") (pinfunction "COMP_1") (pintype "bidirectional"))
    )
    (net (code "33") (name "Net-(R11-P$1)") (class "Default")
      (node (ref "R11") (pin "1") (pinfunction "P$1_1") (pintype "passive"))
      (node (ref "R12") (pin "2") (pinfunction "P$2_2") (pintype "passive"))
      (node (ref "U3") (pin "2") (pinfunction "FB_2") (pintype "bidirectional"))
    )
    (net (code "34") (name "Net-(R13-P$2)") (class "Default")
      (node (ref "C15") (pin "1") (pinfunction "1_1") (pintype "passive"))
      (node (ref "C16") (pin "2") (pinfunction "2_2") (pintype "passive"))
      (node (ref "R13") (pin "2") (pinfunction "P$2_2") (pintype "passive"))
      (node (ref "U4") (pin "3") (pinfunction "T-_3") (pintype "bidirectional"))
    )
    (net (code "35") (name "Net-(R14-P$2)") (class "Default")
      (node (ref "C16") (pin "1") (pinfunction "1_1") (pintype "passive"))
      (node (ref "C17") (pin "2") (pinfunction "2_2") (pintype "passive"))
      (node (ref "R14") (pin "2") (pinfunction "P$2_2") (pintype "passive"))
      (node (ref "U4") (pin "4") (pinfunction "T+_4") (pintype "bidirectional"))
    )
    (net (code "36") (name "Net-(R15-P$2)") (class "Default")
      (node (ref "C18") (pin "1") (pinfunction "1_1") (pintype "passive"))
      (node (ref "C19") (pin "2") (pinfunction "2_2") (pintype "passive"))
      (node (ref "R15") (pin "2") (pinfunction "P$2_2") (pintype "passive"))
      (node (ref "U5") (pin "3") (pinfunction "T-_3") (pintype "bidirectional"))
    )
    (net (code "37") (name "Net-(R16-P$2)") (class "Default")
      (node (ref "C19") (pin "1") (pinfunction "1_1") (pintype "passive"))
      (node (ref "C20") (pin "2") (pinfunction "2_2") (pintype "passive"))
      (node (ref "R16") (pin "2") (pinfunction "P$2_2") (pintype "passive"))
      (node (ref "U5") (pin "4") (pinfunction "T+_4") (pintype "bidirectional"))
    )
    (net (code "38") (name "Net-(R17-P$2)") (class "Default")
      (node (ref "C25") (pin "1") (pinfunction "1_1") (pintype "passive"))
      (node (ref "C26") (pin "2") (pinfunction "2_2") (pintype "passive"))
      (node (ref "R17") (pin "2") (pinfunction "P$2_2") (pintype "passive"))
      (node (ref "U6") (pin "3") (pinfunction "T-_3") (pintype "bidirectional"))
    )
    (net (code "39") (name "Net-(R18-P$2)") (class "Default")
      (node (ref "C26") (pin "1") (pinfunction "1_1") (pintype "passive"))
      (node (ref "C27") (pin "2") (pinfunction "2_2") (pintype "passive"))
      (node (ref "R18") (pin "2") (pinfunction "P$2_2") (pintype "passive"))
      (node (ref "U6") (pin "4") (pinfunction "T+_4") (pintype "bidirectional"))
    )
    (net (code "40") (name "Net-(R20-P$1)") (class "Default")
      (node (ref "R20") (pin "1") (pinfunction "P$1_1") (pintype "passive"))
      (node (ref "U7") (pin "23") (pinfunction "PC0(ADC0)_23") (pintype "bidirectional"))
    )
    (net (code "41") (name "Net-(R20-P$2)") (class "Default")
      (node (ref "D6") (pin "ANODE") (pinfunction "ANODE_ANODE") (pintype "power_in"))
      (node (ref "R20") (pin "2") (pinfunction "P$2_2") (pintype "passive"))
    )
    (net (code "42") (name "Net-(R21-P$1)") (class "Default")
      (node (ref "R21") (pin "1") (pinfunction "P$1_1") (pintype "passive"))
      (node (ref "U7") (pin "13") (pinfunction "PB1(OC1A)_13") (pintype "bidirectional"))
    )
    (net (code "43") (name "Net-(R21-P$2)") (class "Default")
      (node (ref "D7") (pin "ANODE") (pinfunction "ANODE_ANODE") (pintype "power_in"))
      (node (ref "R21") (pin "2") (pinfunction "P$2_2") (pintype "passive"))
    )
    (net (code "44") (name "Net-(U1-SW1)") (class "Default")
      (node (ref "L1") (pin "P$1") (pinfunction "P$1_P$1") (pintype "passive"))
      (node (ref "U1") (pin "4") (pinfunction "SW1_4") (pintype "bidirectional"))
    )
    (net (code "45") (name "Net-(U1-SW2)") (class "Default")
      (node (ref "L1") (pin "P$2") (pinfunction "P$2_P$2") (pintype "passive"))
      (node (ref "U1") (pin "2") (pinfunction "SW2_2") (pintype "bidirectional"))
    )
    (net (code "46") (name "Net-(U3-SS)") (class "Default")
      (node (ref "C8") (pin "1") (pinfunction "1_1") (pintype "passive"))
      (node (ref "U3") (pin "10") (pinfunction "SS_10") (pintype "bidirectional"))
    )
    (net (code "47") (name "Net-(U7-AREF)") (class "Default")
      (node (ref "C30") (pin "1") (pinfunction "1_1") (pintype "passive"))
      (node (ref "U7") (pin "20") (pinfunction "AREF_20") (pintype "bidirectional"))
    )
    (net (code "48") (name "Net-(U7-PB6(XTAL1{slash}TOSC1))") (class "Default")
      (node (ref "U7") (pin "7") (pinfunction "PB6(XTAL1/TOSC1)_7") (pintype "bidirectional"))
      (node (ref "Y1") (pin "1") (pinfunction "1_1") (pintype "passive"))
    )
    (net (code "49") (name "Net-(U7-PB7(XTAL2{slash}TOSC2))") (class "Default")
      (node (ref "U7") (pin "8") (pinfunction "PB7(XTAL2/TOSC2)_8") (pintype "bidirectional"))
      (node (ref "Y1") (pin "3") (pinfunction "3_3") (pintype "passive"))
    )
    (net (code "50") (name "Net-(U8-ANT)") (class "Default")
      (node (ref "ANT1") (pin "1") (pinfunction "1_1") (pintype "bidirectional"))
      (node (ref "U8") (pin "9") (pinfunction "ANT_9") (pintype "passive"))
    )
    (net (code "51") (name "Net-(U8-MOSI)") (class "Default")
      (node (ref "SJ2") (pin "2") (pinfunction "2_2") (pintype "passive"))
      (node (ref "U8") (pin "3") (pinfunction "MOSI_3") (pintype "input"))
    )
    (net (code "52") (name "Net-(U8-SCK)") (class "Default")
      (node (ref "SJ1") (pin "2") (pinfunction "2_2") (pintype "passive"))
      (node (ref "U8") (pin "4") (pinfunction "SCK_4") (pintype "input"))
    )
    (net (code "53") (name "Net-(U9-CLK)") (class "Default")
      (node (ref "SJ3") (pin "1") (pinfunction "1_1") (pintype "passive"))
      (node (ref "U9") (pin "6") (pinfunction "CLK_6") (pintype "bidirectional"))
    )
    (net (code "54") (name "Net-(U9-MOSI)") (class "Default")
      (node (ref "SJ4") (pin "1") (pinfunction "1_1") (pintype "passive"))
      (node (ref "U9") (pin "5") (pinfunction "MOSI_5") (pintype "bidirectional"))
    )
    (net (code "55") (name "PWR_GD") (class "Default")
      (node (ref "U2") (pin "6") (pinfunction "/PG_6") (pintype "output"))
      (node (ref "U7") (pin "19") (pinfunction "ADC6_19") (pintype "bidirectional"))
    )
    (net (code "56") (name "RF_CS") (class "Default")
      (node (ref "U7") (pin "14") (pinfunction "PB2(SS/OC1B)_14") (pintype "bidirectional"))
      (node (ref "U8") (pin "5") (pinfunction "NSS_5") (pintype "input"))
    )
    (net (code "57") (name "RF_INT") (class "Default")
      (node (ref "U7") (pin "32") (pinfunction "PD2(INT0)_32") (pintype "bidirectional"))
      (node (ref "U8") (pin "14") (pinfunction "DIO0_14") (pintype "bidirectional"))
    )
    (net (code "58") (name "RST") (class "Default")
      (node (ref "C31") (pin "2") (pinfunction "2_2") (pintype "passive"))
      (node (ref "R19") (pin "2") (pinfunction "P$2_2") (pintype "passive"))
      (node (ref "TC1") (pin "P$5") (pinfunction "PIN5_P$5") (pintype "bidirectional"))
      (node (ref "U7") (pin "29") (pinfunction "PC6(/RESET)_29") (pintype "bidirectional"))
    )
    (net (code "59") (name "RX") (class "Default")
      (node (ref "J6") (pin "3") (pinfunction "TXO_3") (pintype "passive"))
      (node (ref "U7") (pin "30") (pinfunction "PD0(RXD)_30") (pintype "bidirectional"))
    )
    (net (code "60") (name "SCK") (class "Default")
      (node (ref "SJ1") (pin "1") (pinfunction "1_1") (pintype "passive"))
      (node (ref "SJ3") (pin "2") (pinfunction "2_2") (pintype "passive"))
      (node (ref "TC1") (pin "P$3") (pinfunction "PIN3_P$3") (pintype "bidirectional"))
      (node (ref "U4") (pin "10") (pinfunction "SCK_10") (pintype "bidirectional"))
      (node (ref "U5") (pin "10") (pinfunction "SCK_10") (pintype "bidirectional"))
      (node (ref "U6") (pin "10") (pinfunction "SCK_10") (pintype "bidirectional"))
      (node (ref "U7") (pin "17") (pinfunction "PB5(SCK)_17") (pintype "bidirectional"))
    )
    (net (code "61") (name "TC1_CS") (class "Default")
      (node (ref "U4") (pin "9") (pinfunction "CS_9") (pintype "bidirectional"))
      (node (ref "U7") (pin "11") (pinfunction "PD7(AIN1)_11") (pintype "bidirectional"))
    )
    (net (code "62") (name "TC2_CS") (class "Default")
      (node (ref "U6") (pin "9") (pinfunction "CS_9") (pintype "bidirectional"))
      (node (ref "U7") (pin "10") (pinfunction "PD6(AIN0)_10") (pintype "bidirectional"))
    )
    (net (code "63") (name "TC2_NEG") (class "Default")
      (node (ref "J5") (pin "NEG") (pinfunction "PIN1_NEG") (pintype "bidirectional"))
      (node (ref "R17") (pin "1") (pinfunction "P$1_1") (pintype "passive"))
      (node (ref "U6") (pin "2") (pinfunction "BIAS_2") (pintype "bidirectional"))
    )
    (net (code "64") (name "TC3_CS") (class "Default")
      (node (ref "U5") (pin "9") (pinfunction "CS_9") (pintype "bidirectional"))
      (node (ref "U7") (pin "9") (pinfunction "PD5(T1)_9") (pintype "bidirectional"))
    )
    (net (code "65") (name "TX") (class "Default")
      (node (ref "J6") (pin "2") (pinfunction "RXI_2") (pintype "passive"))
      (node (ref "U7") (pin "31") (pinfunction "PD1(TXD)_31") (pintype "bidirectional"))
    )
    (net (code "66") (name "V_BAT") (class "Default")
      (node (ref "BATT1") (pin "POS_1") (pinfunction "VBAT_POS_1") (pintype "bidirectional"))
      (node (ref "BATT1") (pin "POS_2") (pinfunction "VBAT_POS_2") (pintype "bidirectional"))
      (node (ref "BATT1") (pin "POS_3") (pinfunction "VBAT_POS_3") (pintype "bidirectional"))
      (node (ref "C1") (pin "1") (pinfunction "1_1") (pintype "passive"))
      (node (ref "C5") (pin "1") (pinfunction "1_1") (pintype "passive"))
      (node (ref "C6") (pin "2") (pinfunction "2_2") (pintype "passive"))
      (node (ref "C7") (pin "1") (pinfunction "1_1") (pintype "passive"))
      (node (ref "L2") (pin "1") (pinfunction "P$1_1") (pintype "passive"))
      (node (ref "Q3") (pin "2") (pinfunction "S_2") (pintype "passive"))
      (node (ref "R22") (pin "2") (pinfunction "P$2_2") (pintype "passive"))
      (node (ref "U1") (pin "5") (pinfunction "PVIN_5") (pintype "bidirectional"))
      (node (ref "U1") (pin "6") (pinfunction "EN_6") (pintype "bidirectional"))
      (node (ref "U1") (pin "8") (pinfunction "VIN_8") (pintype "bidirectional"))
      (node (ref "U2") (pin "14") (pinfunction "VBAT1_14") (pintype "output"))
      (node (ref "U2") (pin "15") (pinfunction "VBAT2_15") (pintype "output"))
      (node (ref "U2") (pin "16") (pinfunction "VBAT3_16") (pintype "output"))
      (node (ref "U3") (pin "8") (pinfunction "VIN_8") (pintype "bidirectional"))
    )
    (net (code "67") (name "V_LOAD") (class "Default")
      (node (ref "C4") (pin "1") (pinfunction "1_1") (pintype "passive"))
      (node (ref "U2") (pin "1") (pinfunction "OUT1_1") (pintype "output"))
      (node (ref "U2") (pin "20") (pinfunction "OUT2_20") (pintype "output"))
    )
    (net (code "68") (name "V_SOLAR") (class "Default")
      (node (ref "C11") (pin "POS") (pinfunction "POS_POS") (pintype "passive"))
      (node (ref "C12") (pin "1") (pinfunction "1_1") (pintype "passive"))
      (node (ref "D4") (pin "C") (pinfunction "C_C") (pintype "passive"))
      (node (ref "R4") (pin "2") (pinfunction "P$2_2") (pintype "passive"))
      (node (ref "U2") (pin "17") (pinfunction "CE_17") (pintype "input"))
      (node (ref "U2") (pin "18") (pinfunction "IN1_18") (pintype "input"))
      (node (ref "U2") (pin "19") (pinfunction "IN2_19") (pintype "input"))
      (node (ref "U2") (pin "3") (pinfunction "SEL_3") (pintype "input"))
      (node (ref "U2") (pin "4") (pinfunction "PROG2_4") (pintype "input"))
      (node (ref "U2") (pin "9") (pinfunction "/TE_9") (pintype "input"))
    )
    (net (code "69") (name "unconnected-(J6-CTS-Pad5)") (class "Default")
      (node (ref "J6") (pin "5") (pinfunction "CTS_5") (pintype "passive"))
    )
    (net (code "70") (name "unconnected-(U2-STAT1{slash}LBO-Pad8)") (class "Default")
      (node (ref "U2") (pin "8") (pinfunction "STAT1/LBO_8") (pintype "output"))
    )
    (net (code "71") (name "unconnected-(U2-STAT2-Pad7)") (class "Default")
      (node (ref "U2") (pin "7") (pinfunction "STAT2_7") (pintype "output"))
    )
    (net (code "72") (name "unconnected-(U4-DNC-Pad6)") (class "Default")
      (node (ref "U4") (pin "6") (pinfunction "DNC_6") (pintype "bidirectional"))
    )
    (net (code "73") (name "unconnected-(U4-DRDY-Pad7)") (class "Default")
      (node (ref "U4") (pin "7") (pinfunction "DRDY_7") (pintype "bidirectional"))
    )
    (net (code "74") (name "unconnected-(U4-FAULT-Pad13)") (class "Default")
      (node (ref "U4") (pin "13") (pinfunction "FAULT_13") (pintype "bidirectional"))
    )
    (net (code "75") (name "unconnected-(U5-DNC-Pad6)") (class "Default")
      (node (ref "U5") (pin "6") (pinfunction "DNC_6") (pintype "bidirectional"))
    )
    (net (code "76") (name "unconnected-(U5-DRDY-Pad7)") (class "Default")
      (node (ref "U5") (pin "7") (pinfunction "DRDY_7") (pintype "bidirectional"))
    )
    (net (code "77") (name "unconnected-(U5-FAULT-Pad13)") (class "Default")
      (node (ref "U5") (pin "13") (pinfunction "FAULT_13") (pintype "bidirectional"))
    )
    (net (code "78") (name "unconnected-(U6-DNC-Pad6)") (class "Default")
      (node (ref "U6") (pin "6") (pinfunction "DNC_6") (pintype "bidirectional"))
    )
    (net (code "79") (name "unconnected-(U6-DRDY-Pad7)") (class "Default")
      (node (ref "U6") (pin "7") (pinfunction "DRDY_7") (pintype "bidirectional"))
    )
    (net (code "80") (name "unconnected-(U6-FAULT-Pad13)") (class "Default")
      (node (ref "U6") (pin "13") (pinfunction "FAULT_13") (pintype "bidirectional"))
    )
    (net (code "81") (name "unconnected-(U8-DIO1-Pad15)") (class "Default")
      (node (ref "U8") (pin "15") (pinfunction "DIO1_15") (pintype "bidirectional"))
    )
    (net (code "82") (name "unconnected-(U8-DIO2-Pad16)") (class "Default")
      (node (ref "U8") (pin "16") (pinfunction "DIO2_16") (pintype "bidirectional"))
    )
    (net (code "83") (name "unconnected-(U8-DIO3-Pad11)") (class "Default")
      (node (ref "U8") (pin "11") (pinfunction "DIO3_11") (pintype "bidirectional"))
    )
    (net (code "84") (name "unconnected-(U8-DIO4-Pad12)") (class "Default")
      (node (ref "U8") (pin "12") (pinfunction "DIO4_12") (pintype "bidirectional"))
    )
    (net (code "85") (name "unconnected-(U8-DIO5-Pad7)") (class "Default")
      (node (ref "U8") (pin "7") (pinfunction "DIO5_7") (pintype "bidirectional"))
    )
    (net (code "86") (name "unconnected-(U8-RESET-Pad6)") (class "Default")
      (node (ref "U8") (pin "6") (pinfunction "RESET_6") (pintype "input"))
    )
  )
)
